# barbuddy_4layer.net
KiCad netlist of a schematic drawn in EAGLE
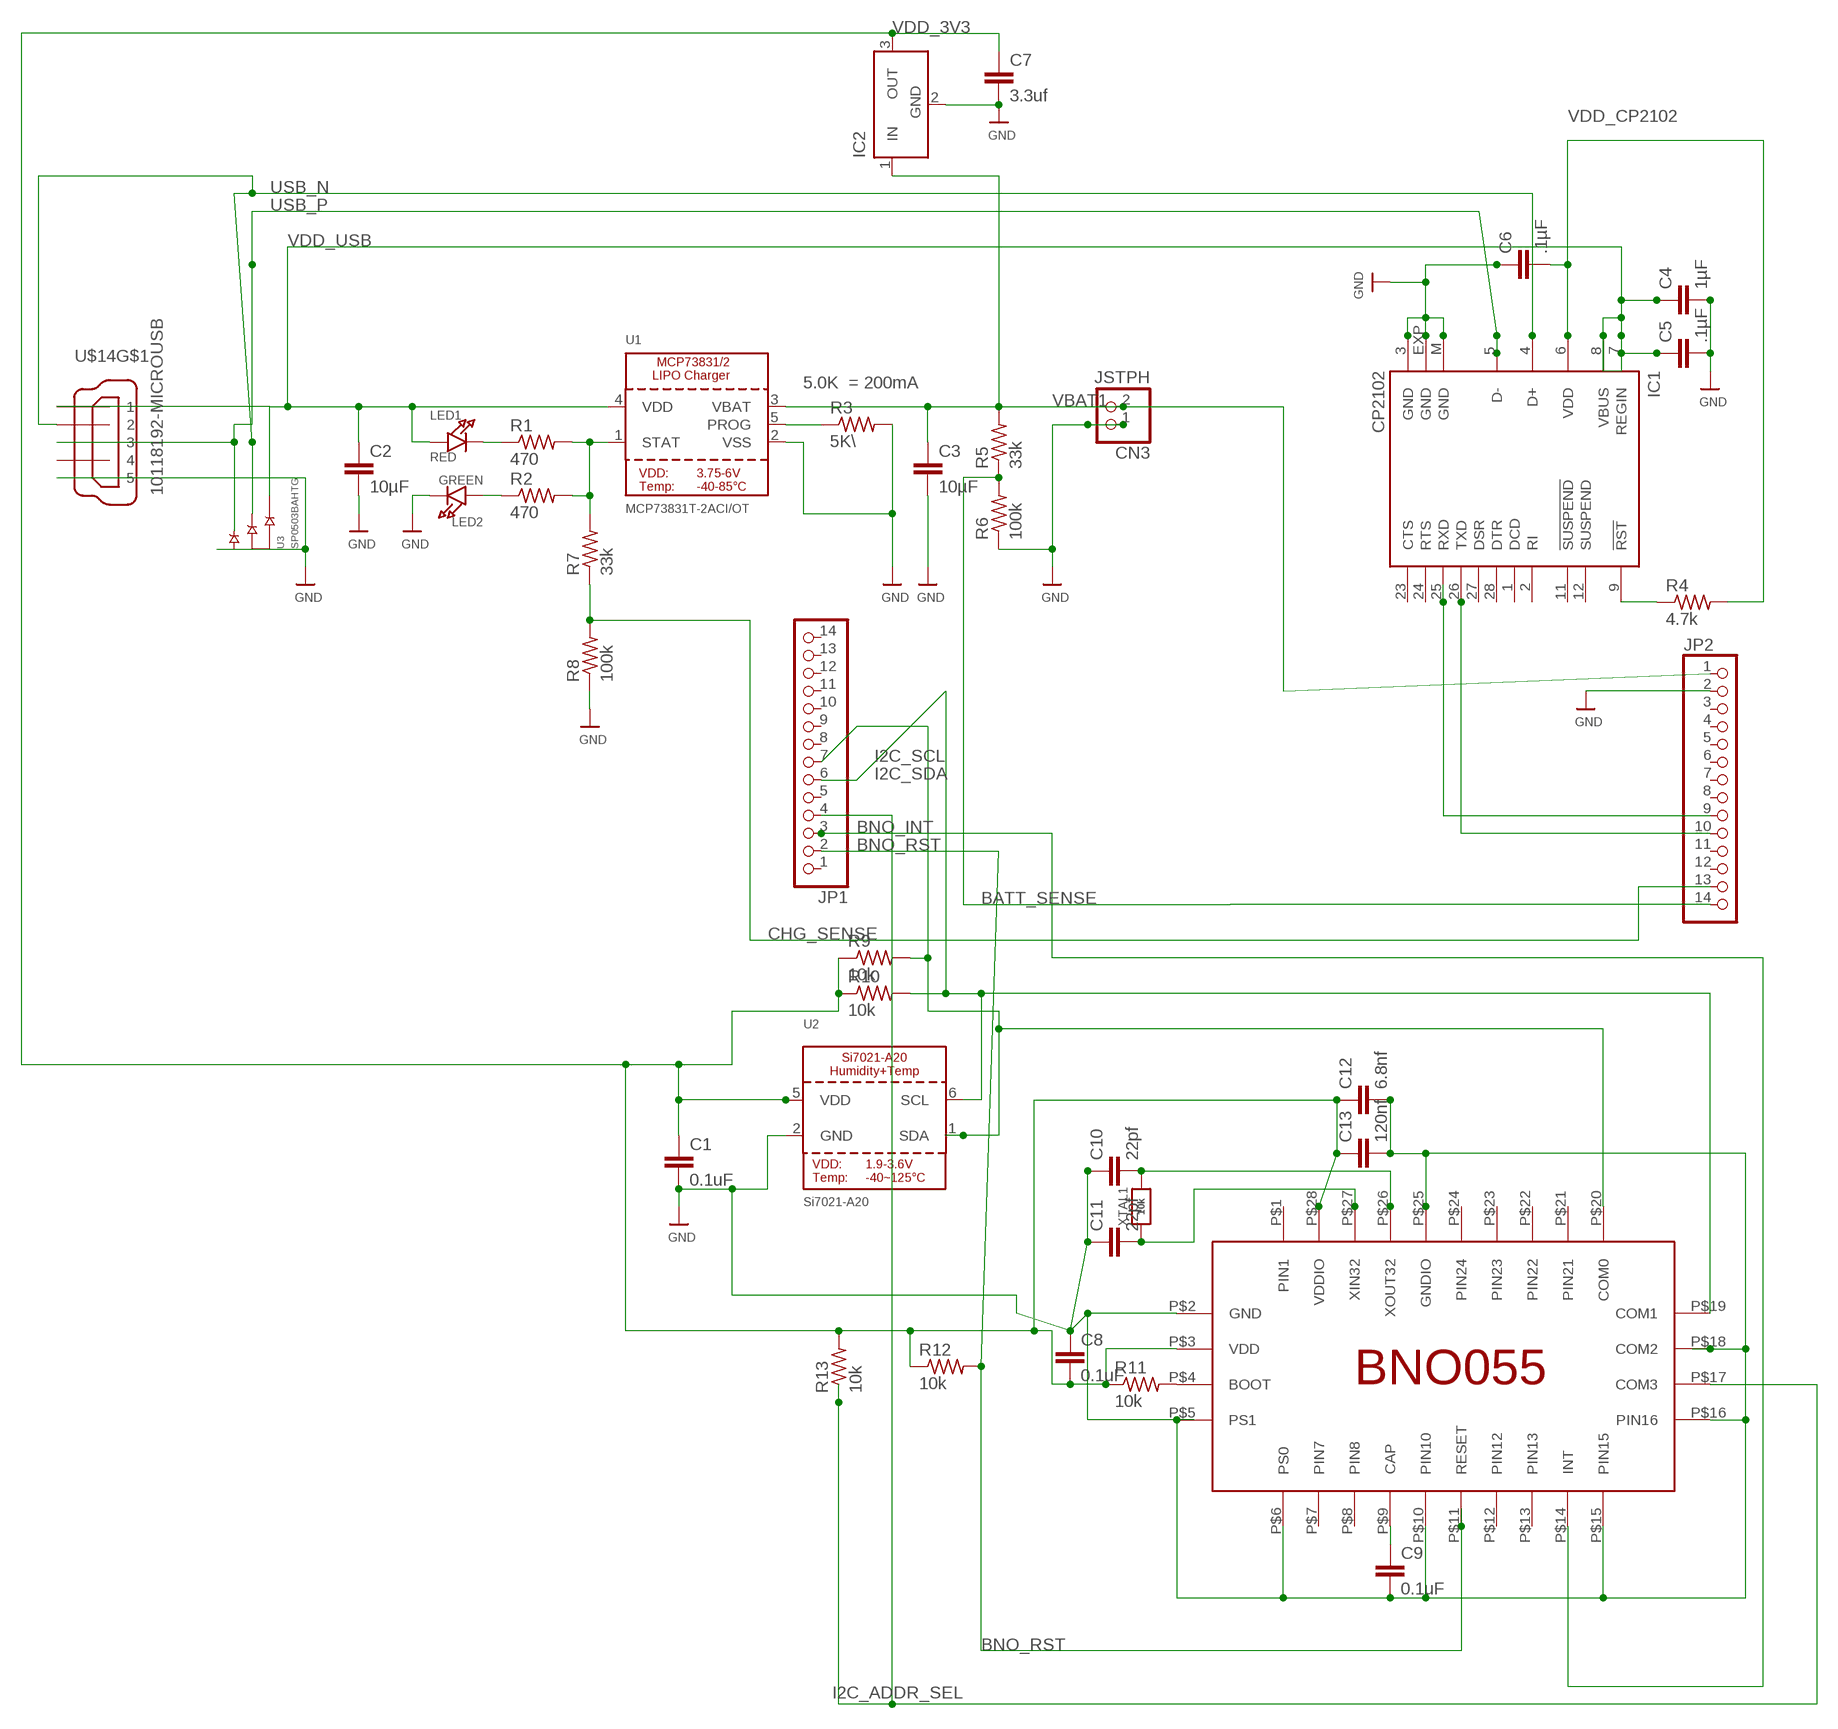
[diagram p0: schematic, sheet 1]

(export (version "E")
  (design (tool "Eeschema 10.0.6"))
  (components
    (comp (ref "BNO055")
      (value "BNO055")
      (footprint "eagle-import:LGA-28")
      (libsource (lib "eagle-import") (part "BNO055"))
    )
    (comp (ref "C1")
      (value "0.1uF")
      (footprint "eagle-import:C0402")
      (libsource (lib "eagle-import") (part "C-EUC0402"))
    )
    (comp (ref "C2")
      (value "10µF")
      (footprint "eagle-import:C0402")
      (libsource (lib "eagle-import") (part "C-EUC0402"))
    )
    (comp (ref "C3")
      (value "10µF")
      (footprint "eagle-import:C0402")
      (libsource (lib "eagle-import") (part "C-EUC0402"))
    )
    (comp (ref "C4")
      (value "1µF")
      (footprint "eagle-import:C0402")
      (libsource (lib "eagle-import") (part "C-EUC0402"))
    )
    (comp (ref "C5")
      (value ".1µF")
      (footprint "eagle-import:C0402")
      (libsource (lib "eagle-import") (part "C-EUC0402"))
    )
    (comp (ref "C6")
      (value ".1µF")
      (footprint "eagle-import:C0402")
      (libsource (lib "eagle-import") (part "C-EUC0402"))
    )
    (comp (ref "C7")
      (value "3.3uf")
      (footprint "eagle-import:C0402")
      (libsource (lib "eagle-import") (part "C-EUC0402"))
    )
    (comp (ref "C8")
      (value "0.1uF")
      (footprint "eagle-import:C0402")
      (libsource (lib "eagle-import") (part "C-EUC0402"))
    )
    (comp (ref "C9")
      (value "0.1uF")
      (footprint "eagle-import:C0402")
      (libsource (lib "eagle-import") (part "C-EUC0402"))
    )
    (comp (ref "C10")
      (value "22pf")
      (footprint "eagle-import:C0402")
      (libsource (lib "eagle-import") (part "C-EUC0402"))
    )
    (comp (ref "C11")
      (value "22pf")
      (footprint "eagle-import:C0402")
      (libsource (lib "eagle-import") (part "C-EUC0402"))
    )
    (comp (ref "C12")
      (value "6.8nf")
      (footprint "eagle-import:C0402")
      (libsource (lib "eagle-import") (part "C-EUC0402"))
    )
    (comp (ref "C13")
      (value "120nf")
      (footprint "eagle-import:C0402")
      (libsource (lib "eagle-import") (part "C-EUC0402"))
    )
    (comp (ref "CN3")
      (value "JSTPH")
      (footprint "eagle-import:JSTPH2")
      (libsource (lib "eagle-import") (part "JST_2PIN"))
    )
    (comp (ref "IC1")
      (value "CP2102")
      (footprint "eagle-import:MLP28")
      (fields (field (name "MF") "FARNELL") (field (name "MPN") "CP2102-GM"))
      (libsource (lib "eagle-import") (part "CP2102"))
    )
    (comp (ref "IC2")
      (value "LT1129CST5")
      (footprint "eagle-import:SOT223")
      (libsource (lib "eagle-import") (part "LT1129CST5"))
    )
    (comp (ref "JP1")
      (value "PINHD-1X14")
      (footprint "eagle-import:1X14")
      (libsource (lib "eagle-import") (part "PINHD-1X14"))
    )
    (comp (ref "JP2")
      (value "PINHD-1X14")
      (footprint "eagle-import:1X14")
      (libsource (lib "eagle-import") (part "PINHD-1X14"))
    )
    (comp (ref "LED1")
      (value "RED")
      (footprint "eagle-import:CHIPLED_0805_NOOUTLINE")
      (libsource (lib "eagle-import") (part "LED0805_NOOUTLINE"))
    )
    (comp (ref "LED2")
      (value "GREEN")
      (footprint "eagle-import:CHIPLED_0805_NOOUTLINE")
      (libsource (lib "eagle-import") (part "LED0805_NOOUTLINE"))
    )
    (comp (ref "R1")
      (value "470")
      (footprint "eagle-import:R0402")
      (libsource (lib "eagle-import") (part "R-US_R0402"))
    )
    (comp (ref "R2")
      (value "470")
      (footprint "eagle-import:R0402")
      (libsource (lib "eagle-import") (part "R-US_R0402"))
    )
    (comp (ref "R3")
      (value "5K\\")
      (footprint "eagle-import:R0402")
      (libsource (lib "eagle-import") (part "R-US_R0402"))
    )
    (comp (ref "R4")
      (value "4.7k")
      (footprint "eagle-import:R0402")
      (libsource (lib "eagle-import") (part "R-US_R0402"))
    )
    (comp (ref "R5")
      (value "33k")
      (footprint "eagle-import:R0402")
      (libsource (lib "eagle-import") (part "R-US_R0402"))
    )
    (comp (ref "R6")
      (value "100k")
      (footprint "eagle-import:R0402")
      (libsource (lib "eagle-import") (part "R-US_R0402"))
    )
    (comp (ref "R7")
      (value "33k")
      (footprint "eagle-import:R0402")
      (libsource (lib "eagle-import") (part "R-US_R0402"))
    )
    (comp (ref "R8")
      (value "100k")
      (footprint "eagle-import:R0402")
      (libsource (lib "eagle-import") (part "R-US_R0402"))
    )
    (comp (ref "R9")
      (value "10k")
      (footprint "eagle-import:R0402")
      (libsource (lib "eagle-import") (part "R-US_R0402"))
    )
    (comp (ref "R10")
      (value "10k")
      (footprint "eagle-import:R0402")
      (libsource (lib "eagle-import") (part "R-US_R0402"))
    )
    (comp (ref "R11")
      (value "10k")
      (footprint "eagle-import:R0402")
      (libsource (lib "eagle-import") (part "R-US_R0402"))
    )
    (comp (ref "R12")
      (value "10k")
      (footprint "eagle-import:R0402")
      (libsource (lib "eagle-import") (part "R-US_R0402"))
    )
    (comp (ref "R13")
      (value "10k")
      (footprint "eagle-import:R0402")
      (libsource (lib "eagle-import") (part "R-US_R0402"))
    )
    (comp (ref "U$14")
      (value "10118192-MICROUSB")
      (footprint "eagle-import:MICROUSB-SMT")
      (libsource (lib "eagle-import") (part "10118192-MICROUSB"))
    )
    (comp (ref "U1")
      (value "MCP73831T-2ACI/OT")
      (footprint "eagle-import:SOT23-5")
      (libsource (lib "eagle-import") (part "MCP73831/2"))
    )
    (comp (ref "U2")
      (value "Si7021-A20")
      (footprint "eagle-import:DFN6_3X3_SI")
      (libsource (lib "eagle-import") (part "SI7021-A20"))
    )
    (comp (ref "U3")
      (value "SP0503BAHTG")
      (footprint "eagle-import:SOT143")
      (libsource (lib "eagle-import") (part "SP0503BAHTG"))
    )
    (comp (ref "XTAL1")
      (value "10k")
      (footprint "eagle-import:0805-NO")
      (libsource (lib "eagle-import") (part "RESISTOR0805_NOOUTLINE"))
    )
  )
  (nets
    (net (code "1") (name "/BATT_SENSE") (class "Default")
      (node (ref "JP2") (pin "14") (pinfunction "14_14") (pintype "passive"))
      (node (ref "R5") (pin "1") (pinfunction "1_1") (pintype "passive"))
      (node (ref "R6") (pin "2") (pinfunction "2_2") (pintype "passive"))
    )
    (net (code "2") (name "/BNO_INT") (class "Default")
      (node (ref "BNO055") (pin "P$14") (pinfunction "INT_P$14") (pintype "bidirectional"))
      (node (ref "JP1") (pin "3") (pinfunction "3_3") (pintype "passive"))
    )
    (net (code "3") (name "/BNO_RST") (class "Default")
      (node (ref "BNO055") (pin "P$11") (pinfunction "RESET_P$11") (pintype "bidirectional"))
      (node (ref "JP1") (pin "2") (pinfunction "2_2") (pintype "passive"))
      (node (ref "R12") (pin "2") (pinfunction "2_2") (pintype "passive"))
    )
    (net (code "4") (name "/CHG_SENSE") (class "Default")
      (node (ref "JP2") (pin "13") (pinfunction "13_13") (pintype "passive"))
      (node (ref "R7") (pin "1") (pinfunction "1_1") (pintype "passive"))
      (node (ref "R8") (pin "2") (pinfunction "2_2") (pintype "passive"))
    )
    (net (code "5") (name "/I2C_ADDR_SEL") (class "Default")
      (node (ref "BNO055") (pin "P$17") (pinfunction "COM3_P$17") (pintype "bidirectional"))
      (node (ref "JP1") (pin "4") (pinfunction "4_4") (pintype "passive"))
      (node (ref "R13") (pin "1") (pinfunction "1_1") (pintype "passive"))
    )
    (net (code "6") (name "/I2C_SCL") (class "Default")
      (node (ref "BNO055") (pin "P$19") (pinfunction "COM1_P$19") (pintype "bidirectional"))
      (node (ref "JP1") (pin "6") (pinfunction "6_6") (pintype "passive"))
      (node (ref "R10") (pin "2") (pinfunction "2_2") (pintype "passive"))
      (node (ref "U2") (pin "6") (pinfunction "SCL_6") (pintype "open_collector"))
    )
    (net (code "7") (name "/I2C_SDA") (class "Default")
      (node (ref "BNO055") (pin "P$20") (pinfunction "COM0_P$20") (pintype "bidirectional"))
      (node (ref "JP1") (pin "7") (pinfunction "7_7") (pintype "passive"))
      (node (ref "R9") (pin "2") (pinfunction "2_2") (pintype "passive"))
      (node (ref "U2") (pin "1") (pinfunction "SDA_1") (pintype "open_collector"))
    )
    (net (code "8") (name "/USB_N") (class "Default")
      (node (ref "IC1") (pin "4") (pinfunction "D+_4") (pintype "bidirectional"))
      (node (ref "U$14") (pin "P$2") (pinfunction "2_P$2") (pintype "input"))
      (node (ref "U3") (pin "3") (pinfunction "B_3") (pintype "bidirectional"))
    )
    (net (code "9") (name "/USB_P") (class "Default")
      (node (ref "IC1") (pin "5") (pinfunction "D-_5") (pintype "bidirectional"))
      (node (ref "U$14") (pin "P$3") (pinfunction "3_P$3") (pintype "input"))
      (node (ref "U3") (pin "2") (pinfunction "A_2") (pintype "bidirectional"))
    )
    (net (code "10") (name "/VBAT1") (class "Default")
      (node (ref "C3") (pin "1") (pinfunction "1_1") (pintype "passive"))
      (node (ref "CN3") (pin "2") (pinfunction "2_2") (pintype "passive"))
      (node (ref "IC2") (pin "1") (pinfunction "IN_1") (pintype "input"))
      (node (ref "JP2") (pin "1") (pinfunction "1_1") (pintype "passive"))
      (node (ref "R5") (pin "2") (pinfunction "2_2") (pintype "passive"))
      (node (ref "U1") (pin "3") (pinfunction "VBAT_3") (pintype "power_in"))
    )
    (net (code "11") (name "/VDD_3V3") (class "Default")
      (node (ref "BNO055") (pin "P$28") (pinfunction "VDDIO_P$28") (pintype "bidirectional"))
      (node (ref "BNO055") (pin "P$3") (pinfunction "VDD_P$3") (pintype "bidirectional"))
      (node (ref "C1") (pin "1") (pinfunction "1_1") (pintype "passive"))
      (node (ref "C12") (pin "1") (pinfunction "1_1") (pintype "passive"))
      (node (ref "C13") (pin "1") (pinfunction "1_1") (pintype "passive"))
      (node (ref "C7") (pin "1") (pinfunction "1_1") (pintype "passive"))
      (node (ref "C8") (pin "2") (pinfunction "2_2") (pintype "passive"))
      (node (ref "IC2") (pin "3") (pinfunction "OUT_3") (pintype "output"))
      (node (ref "R10") (pin "1") (pinfunction "1_1") (pintype "passive"))
      (node (ref "R11") (pin "1") (pinfunction "1_1") (pintype "passive"))
      (node (ref "R12") (pin "1") (pinfunction "1_1") (pintype "passive"))
      (node (ref "R13") (pin "2") (pinfunction "2_2") (pintype "passive"))
      (node (ref "R9") (pin "1") (pinfunction "1_1") (pintype "passive"))
      (node (ref "U2") (pin "5") (pinfunction "VDD_5") (pintype "power_in"))
    )
    (net (code "12") (name "/VDD_CP2102") (class "Default")
      (node (ref "C6") (pin "2") (pinfunction "2_2") (pintype "passive"))
      (node (ref "IC1") (pin "6") (pinfunction "VDD_6") (pintype "power_in"))
      (node (ref "R4") (pin "2") (pinfunction "2_2") (pintype "passive"))
    )
    (net (code "13") (name "/VDD_USB") (class "Default")
      (node (ref "C2") (pin "1") (pinfunction "1_1") (pintype "passive"))
      (node (ref "C4") (pin "1") (pinfunction "1_1") (pintype "passive"))
      (node (ref "C5") (pin "1") (pinfunction "1_1") (pintype "passive"))
      (node (ref "IC1") (pin "7") (pinfunction "REGIN_7") (pintype "passive"))
      (node (ref "IC1") (pin "8") (pinfunction "VBUS_8") (pintype "input"))
      (node (ref "LED1") (pin "A") (pinfunction "A_A") (pintype "passive"))
      (node (ref "U$14") (pin "P$1") (pinfunction "1_P$1") (pintype "input"))
      (node (ref "U1") (pin "4") (pinfunction "VDD_4") (pintype "power_in"))
      (node (ref "U3") (pin "4") (pinfunction "C_4") (pintype "bidirectional"))
    )
    (net (code "14") (name "GND") (class "Default")
      (node (ref "BNO055") (pin "P$10") (pinfunction "PIN10_P$10") (pintype "bidirectional"))
      (node (ref "BNO055") (pin "P$15") (pinfunction "PIN15_P$15") (pintype "bidirectional"))
      (node (ref "BNO055") (pin "P$16") (pinfunction "PIN16_P$16") (pintype "bidirectional"))
      (node (ref "BNO055") (pin "P$18") (pinfunction "COM2_P$18") (pintype "bidirectional"))
      (node (ref "BNO055") (pin "P$2") (pinfunction "GND_P$2") (pintype "bidirectional"))
      (node (ref "BNO055") (pin "P$25") (pinfunction "GNDIO_P$25") (pintype "bidirectional"))
      (node (ref "BNO055") (pin "P$5") (pinfunction "PS1_P$5") (pintype "bidirectional"))
      (node (ref "BNO055") (pin "P$6") (pinfunction "PS0_P$6") (pintype "bidirectional"))
      (node (ref "C1") (pin "2") (pinfunction "2_2") (pintype "passive"))
      (node (ref "C10") (pin "1") (pinfunction "1_1") (pintype "passive"))
      (node (ref "C11") (pin "1") (pinfunction "1_1") (pintype "passive"))
      (node (ref "C12") (pin "2") (pinfunction "2_2") (pintype "passive"))
      (node (ref "C13") (pin "2") (pinfunction "2_2") (pintype "passive"))
      (node (ref "C2") (pin "2") (pinfunction "2_2") (pintype "passive"))
      (node (ref "C3") (pin "2") (pinfunction "2_2") (pintype "passive"))
      (node (ref "C4") (pin "2") (pinfunction "2_2") (pintype "passive"))
      (node (ref "C5") (pin "2") (pinfunction "2_2") (pintype "passive"))
      (node (ref "C6") (pin "1") (pinfunction "1_1") (pintype "passive"))
      (node (ref "C7") (pin "2") (pinfunction "2_2") (pintype "passive"))
      (node (ref "C8") (pin "1") (pinfunction "1_1") (pintype "passive"))
      (node (ref "C9") (pin "2") (pinfunction "2_2") (pintype "passive"))
      (node (ref "CN3") (pin "1") (pinfunction "1_1") (pintype "passive"))
      (node (ref "IC1") (pin "3") (pinfunction "GND_3") (pintype "power_in"))
      (node (ref "IC1") (pin "EXP") (pinfunction "GND_EXP") (pintype "power_in"))
      (node (ref "IC1") (pin "M") (pinfunction "GND_M") (pintype "power_in"))
      (node (ref "IC2") (pin "2") (pinfunction "GND_2") (pintype "power_in"))
      (node (ref "JP2") (pin "2") (pinfunction "2_2") (pintype "passive"))
      (node (ref "LED2") (pin "C") (pinfunction "C_C") (pintype "passive"))
      (node (ref "R3") (pin "2") (pinfunction "2_2") (pintype "passive"))
      (node (ref "R6") (pin "1") (pinfunction "1_1") (pintype "passive"))
      (node (ref "R8") (pin "1") (pinfunction "1_1") (pintype "passive"))
      (node (ref "U$14") (pin "P$5") (pinfunction "5_P$5") (pintype "input"))
      (node (ref "U1") (pin "2") (pinfunction "VSS_2") (pintype "power_in"))
      (node (ref "U2") (pin "2") (pinfunction "GND_2") (pintype "power_in"))
      (node (ref "U3") (pin "1") (pinfunction "GND_1") (pintype "bidirectional"))
    )
    (net (code "15") (name "Net-(BNO055-BOOT)") (class "Default")
      (node (ref "BNO055") (pin "P$4") (pinfunction "BOOT_P$4") (pintype "bidirectional"))
      (node (ref "R11") (pin "2") (pinfunction "2_2") (pintype "passive"))
    )
    (net (code "16") (name "Net-(BNO055-CAP)") (class "Default")
      (node (ref "BNO055") (pin "P$9") (pinfunction "CAP_P$9") (pintype "bidirectional"))
      (node (ref "C9") (pin "1") (pinfunction "1_1") (pintype "passive"))
    )
    (net (code "17") (name "Net-(BNO055-XIN32)") (class "Default")
      (node (ref "BNO055") (pin "P$27") (pinfunction "XIN32_P$27") (pintype "bidirectional"))
      (node (ref "C11") (pin "2") (pinfunction "2_2") (pintype "passive"))
      (node (ref "XTAL1") (pin "1") (pinfunction "1_1") (pintype "passive"))
    )
    (net (code "18") (name "Net-(BNO055-XOUT32)") (class "Default")
      (node (ref "BNO055") (pin "P$26") (pinfunction "XOUT32_P$26") (pintype "bidirectional"))
      (node (ref "C10") (pin "2") (pinfunction "2_2") (pintype "passive"))
      (node (ref "XTAL1") (pin "2") (pinfunction "2_2") (pintype "passive"))
    )
    (net (code "19") (name "Net-(IC1-RXD)") (class "Default")
      (node (ref "IC1") (pin "25") (pinfunction "RXD_25") (pintype "input"))
      (node (ref "JP2") (pin "9") (pinfunction "9_9") (pintype "passive"))
    )
    (net (code "20") (name "Net-(IC1-TXD)") (class "Default")
      (node (ref "IC1") (pin "26") (pinfunction "TXD_26") (pintype "output"))
      (node (ref "JP2") (pin "10") (pinfunction "10_10") (pintype "passive"))
    )
    (net (code "21") (name "Net-(IC1-~{RST})") (class "Default")
      (node (ref "IC1") (pin "9") (pinfunction "~{RST}_9") (pintype "bidirectional"))
      (node (ref "R4") (pin "1") (pinfunction "1_1") (pintype "passive"))
    )
    (net (code "22") (name "Net-(LED1-PadC)") (class "Default")
      (node (ref "LED1") (pin "C") (pinfunction "C_C") (pintype "passive"))
      (node (ref "R1") (pin "1") (pinfunction "1_1") (pintype "passive"))
    )
    (net (code "23") (name "Net-(LED2-PadA)") (class "Default")
      (node (ref "LED2") (pin "A") (pinfunction "A_A") (pintype "passive"))
      (node (ref "R2") (pin "1") (pinfunction "1_1") (pintype "passive"))
    )
    (net (code "24") (name "Net-(U1-PROG)") (class "Default")
      (node (ref "R3") (pin "1") (pinfunction "1_1") (pintype "passive"))
      (node (ref "U1") (pin "5") (pinfunction "PROG_5") (pintype "input"))
    )
    (net (code "25") (name "Net-(U1-STAT)") (class "Default")
      (node (ref "R1") (pin "2") (pinfunction "2_2") (pintype "passive"))
      (node (ref "R2") (pin "2") (pinfunction "2_2") (pintype "passive"))
      (node (ref "R7") (pin "2") (pinfunction "2_2") (pintype "passive"))
      (node (ref "U1") (pin "1") (pinfunction "STAT_1") (pintype "output"))
    )
    (net (code "26") (name "unconnected-(BNO055-PIN1-PadP$1)") (class "Default")
      (node (ref "BNO055") (pin "P$1") (pinfunction "PIN1_P$1") (pintype "bidirectional"))
    )
    (net (code "27") (name "unconnected-(BNO055-PIN7-PadP$7)") (class "Default")
      (node (ref "BNO055") (pin "P$7") (pinfunction "PIN7_P$7") (pintype "bidirectional"))
    )
    (net (code "28") (name "unconnected-(BNO055-PIN8-PadP$8)") (class "Default")
      (node (ref "BNO055") (pin "P$8") (pinfunction "PIN8_P$8") (pintype "bidirectional"))
    )
    (net (code "29") (name "unconnected-(BNO055-PIN12-PadP$12)") (class "Default")
      (node (ref "BNO055") (pin "P$12") (pinfunction "PIN12_P$12") (pintype "bidirectional"))
    )
    (net (code "30") (name "unconnected-(BNO055-PIN13-PadP$13)") (class "Default")
      (node (ref "BNO055") (pin "P$13") (pinfunction "PIN13_P$13") (pintype "bidirectional"))
    )
    (net (code "31") (name "unconnected-(BNO055-PIN21-PadP$21)") (class "Default")
      (node (ref "BNO055") (pin "P$21") (pinfunction "PIN21_P$21") (pintype "bidirectional"))
    )
    (net (code "32") (name "unconnected-(BNO055-PIN22-PadP$22)") (class "Default")
      (node (ref "BNO055") (pin "P$22") (pinfunction "PIN22_P$22") (pintype "bidirectional"))
    )
    (net (code "33") (name "unconnected-(BNO055-PIN23-PadP$23)") (class "Default")
      (node (ref "BNO055") (pin "P$23") (pinfunction "PIN23_P$23") (pintype "bidirectional"))
    )
    (net (code "34") (name "unconnected-(BNO055-PIN24-PadP$24)") (class "Default")
      (node (ref "BNO055") (pin "P$24") (pinfunction "PIN24_P$24") (pintype "bidirectional"))
    )
    (net (code "35") (name "unconnected-(IC1-CTS-Pad23)") (class "Default")
      (node (ref "IC1") (pin "23") (pinfunction "CTS_23") (pintype "input"))
    )
    (net (code "36") (name "unconnected-(IC1-DCD-Pad1)") (class "Default")
      (node (ref "IC1") (pin "1") (pinfunction "DCD_1") (pintype "input"))
    )
    (net (code "37") (name "unconnected-(IC1-DSR-Pad27)") (class "Default")
      (node (ref "IC1") (pin "27") (pinfunction "DSR_27") (pintype "input"))
    )
    (net (code "38") (name "unconnected-(IC1-DTR-Pad28)") (class "Default")
      (node (ref "IC1") (pin "28") (pinfunction "DTR_28") (pintype "output"))
    )
    (net (code "39") (name "unconnected-(IC1-RI-Pad2)") (class "Default")
      (node (ref "IC1") (pin "2") (pinfunction "RI_2") (pintype "input"))
    )
    (net (code "40") (name "unconnected-(IC1-RTS-Pad24)") (class "Default")
      (node (ref "IC1") (pin "24") (pinfunction "RTS_24") (pintype "output"))
    )
    (net (code "41") (name "unconnected-(IC1-SUSPEND-Pad12)") (class "Default")
      (node (ref "IC1") (pin "12") (pinfunction "SUSPEND_12") (pintype "output"))
    )
    (net (code "42") (name "unconnected-(IC1-~{SUSPEND}-Pad11)") (class "Default")
      (node (ref "IC1") (pin "11") (pinfunction "~{SUSPEND}_11") (pintype "output"))
    )
    (net (code "43") (name "unconnected-(JP1-Pad1)") (class "Default")
      (node (ref "JP1") (pin "1") (pinfunction "1_1") (pintype "passive"))
    )
    (net (code "44") (name "unconnected-(JP1-Pad5)") (class "Default")
      (node (ref "JP1") (pin "5") (pinfunction "5_5") (pintype "passive"))
    )
    (net (code "45") (name "unconnected-(JP1-Pad8)") (class "Default")
      (node (ref "JP1") (pin "8") (pinfunction "8_8") (pintype "passive"))
    )
    (net (code "46") (name "unconnected-(JP1-Pad9)") (class "Default")
      (node (ref "JP1") (pin "9") (pinfunction "9_9") (pintype "passive"))
    )
    (net (code "47") (name "unconnected-(JP1-Pad10)") (class "Default")
      (node (ref "JP1") (pin "10") (pinfunction "10_10") (pintype "passive"))
    )
    (net (code "48") (name "unconnected-(JP1-Pad11)") (class "Default")
      (node (ref "JP1") (pin "11") (pinfunction "11_11") (pintype "passive"))
    )
    (net (code "49") (name "unconnected-(JP1-Pad12)") (class "Default")
      (node (ref "JP1") (pin "12") (pinfunction "12_12") (pintype "passive"))
    )
    (net (code "50") (name "unconnected-(JP1-Pad13)") (class "Default")
      (node (ref "JP1") (pin "13") (pinfunction "13_13") (pintype "passive"))
    )
    (net (code "51") (name "unconnected-(JP1-Pad14)") (class "Default")
      (node (ref "JP1") (pin "14") (pinfunction "14_14") (pintype "passive"))
    )
    (net (code "52") (name "unconnected-(JP2-Pad3)") (class "Default")
      (node (ref "JP2") (pin "3") (pinfunction "3_3") (pintype "passive"))
    )
    (net (code "53") (name "unconnected-(JP2-Pad4)") (class "Default")
      (node (ref "JP2") (pin "4") (pinfunction "4_4") (pintype "passive"))
    )
    (net (code "54") (name "unconnected-(JP2-Pad5)") (class "Default")
      (node (ref "JP2") (pin "5") (pinfunction "5_5") (pintype "passive"))
    )
    (net (code "55") (name "unconnected-(JP2-Pad6)") (class "Default")
      (node (ref "JP2") (pin "6") (pinfunction "6_6") (pintype "passive"))
    )
    (net (code "56") (name "unconnected-(JP2-Pad7)") (class "Default")
      (node (ref "JP2") (pin "7") (pinfunction "7_7") (pintype "passive"))
    )
    (net (code "57") (name "unconnected-(JP2-Pad8)") (class "Default")
      (node (ref "JP2") (pin "8") (pinfunction "8_8") (pintype "passive"))
    )
    (net (code "58") (name "unconnected-(JP2-Pad11)") (class "Default")
      (node (ref "JP2") (pin "11") (pinfunction "11_11") (pintype "passive"))
    )
    (net (code "59") (name "unconnected-(JP2-Pad12)") (class "Default")
      (node (ref "JP2") (pin "12") (pinfunction "12_12") (pintype "passive"))
    )
    (net (code "60") (name "unconnected-(U$14A-4-PadP$4)") (class "Default")
      (node (ref "U$14") (pin "P$4") (pinfunction "4_P$4") (pintype "input"))
    )
  )
)
